# mboard.net
KiCad netlist of a schematic drawn in Altium Designer
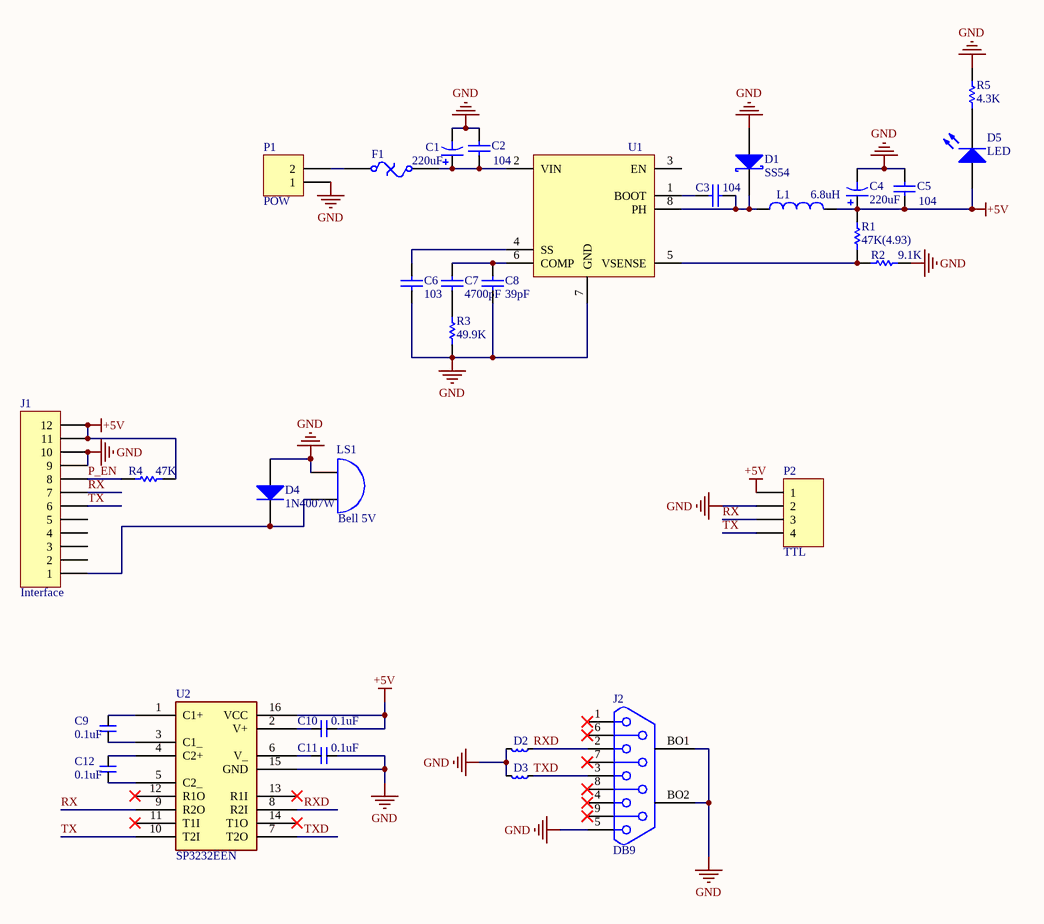
[diagram p0: mboard.SchDoc]

(export (version "E")
  (design (tool "Eeschema 10.0.6"))
  (components
    (comp (ref "C1")
      (value "220uF")
      (footprint "C8x10-SMD")
      (description "Polarized Capacitor (Radial)")
      (fields (field (name "Comment") "Cap Pol1") (field (name "PUBLISHER") "Altium Limited"))
      (libsource (lib "Miscellaneous Devices") (part "Cap Pol1"))
    )
    (comp (ref "C2")
      (value "104")
      (footprint "0603C")
      (description "Capacitor")
      (fields (field (name "Comment") "Cap") (field (name "PUBLISHER") "Altium Limited"))
      (libsource (lib "Miscellaneous Devices") (part "Cap"))
    )
    (comp (ref "C3")
      (value "104")
      (footprint "0603C")
      (description "Capacitor")
      (fields (field (name "Comment") "Cap") (field (name "PUBLISHER") "Altium Limited"))
      (libsource (lib "Miscellaneous Devices") (part "Cap"))
    )
    (comp (ref "C4")
      (value "220uF")
      (footprint "C6.3x5.4-SMD")
      (description "Polarized Capacitor (Radial)")
      (fields (field (name "Comment") "Cap Pol1") (field (name "PUBLISHER") "Altium Limited"))
      (libsource (lib "Miscellaneous Devices") (part "Cap Pol1"))
    )
    (comp (ref "C5")
      (value "104")
      (footprint "0603C")
      (description "Capacitor")
      (fields (field (name "Comment") "Cap") (field (name "PUBLISHER") "Altium Limited"))
      (libsource (lib "Miscellaneous Devices") (part "Cap"))
    )
    (comp (ref "C6")
      (value "103")
      (footprint "0603C")
      (description "Capacitor")
      (fields (field (name "Comment") "Cap") (field (name "PUBLISHER") "Altium Limited"))
      (libsource (lib "Miscellaneous Devices") (part "Cap"))
    )
    (comp (ref "C7")
      (value "4700pF")
      (footprint "0603C")
      (description "Capacitor")
      (fields (field (name "Comment") "Cap") (field (name "PUBLISHER") "Altium Limited"))
      (libsource (lib "Miscellaneous Devices") (part "Cap"))
    )
    (comp (ref "C8")
      (value "39pF")
      (footprint "0603C")
      (description "Capacitor")
      (fields (field (name "Comment") "Cap") (field (name "PUBLISHER") "Altium Limited"))
      (libsource (lib "Miscellaneous Devices") (part "Cap"))
    )
    (comp (ref "C9")
      (value "0.1uF")
      (footprint "0603C")
      (description "电容")
      (libsource (lib "LDT-SCH") (part "电容"))
    )
    (comp (ref "C10")
      (value "0.1uF")
      (footprint "0603C")
      (description "电容")
      (libsource (lib "LDT-SCH") (part "电容"))
    )
    (comp (ref "C11")
      (value "0.1uF")
      (footprint "0603C")
      (description "电容")
      (libsource (lib "LDT-SCH") (part "电容"))
    )
    (comp (ref "C12")
      (value "0.1uF")
      (footprint "0603C")
      (description "电容")
      (libsource (lib "LDT-SCH") (part "电容"))
    )
    (comp (ref "D1")
      (value "SS54")
      (footprint "SMA")
      (description "Schottky Diode")
      (fields (field (name "PUBLISHER") "Altium Limited"))
      (libsource (lib "Miscellaneous Devices") (part "D Schottky"))
    )
    (comp (ref "D2") (value "ESD") (footprint "0603L") (libsource (lib "LDT-SCH") (part "电感")))
    (comp (ref "D3") (value "ESD") (footprint "0603L") (libsource (lib "LDT-SCH") (part "电感")))
    (comp (ref "D4")
      (value "1N4007W")
      (footprint "SOD-123")
      (description "3 Amp Medium Power Silicon Rectifier Diode")
      (fields (field (name "PUBLISHER") "Altium Limited"))
      (libsource (lib "Miscellaneous Devices") (part "Diode 1N5408"))
    )
    (comp (ref "D5")
      (value "LED")
      (footprint "0603-LED")
      (description "Typical RED GaAs LED")
      (fields (field (name "PUBLISHER") "Altium Limited"))
      (libsource (lib "Miscellaneous Devices") (part "LED1"))
    )
    (comp (ref "F1")
      (value "Fuse Thermal")
      (footprint "1812F")
      (description "Thermal Fuse")
      (fields (field (name "PUBLISHER") "Altium Limited"))
      (libsource (lib "Miscellaneous Devices") (part "Fuse Thermal"))
    )
    (comp (ref "J1")
      (value "Interface")
      (footprint "1.25-12P")
      (description "Header, 12-Pin")
      (fields (field (name "PUBLISHER") "Altium Limited"))
      (libsource (lib "Miscellaneous Connectors") (part "Header 12"))
    )
    (comp (ref "J2") (value "DB9") (footprint "DB-9/M") (libsource (lib "LDT-SCH") (part "DB9")))
    (comp (ref "L1")
      (value "6.8uH")
      (footprint "L-6045")
      (description "Inductor")
      (fields (field (name "PUBLISHER") "Altium Limited"))
      (libsource (lib "Miscellaneous Devices") (part "Inductor"))
    )
    (comp (ref "LS1")
      (value "Bell 5V")
      (footprint "BEEP-9x5.5")
      (description "Electrical Bell")
      (fields (field (name "Comment") "Bell") (field (name "PUBLISHER") "Altium Limited"))
      (libsource (lib "Miscellaneous Devices") (part "Bell"))
    )
    (comp (ref "P1")
      (value "POW")
      (footprint "DC-5525")
      (description "Header, 2-Pin")
      (fields (field (name "PUBLISHER") "Altium Limited"))
      (libsource (lib "Miscellaneous Connectors") (part "Header 2"))
    )
    (comp (ref "P2")
      (value "TTL")
      (footprint "XH2.54-4P")
      (description "Header, 4-Pin")
      (fields (field (name "PUBLISHER") "Altium Limited"))
      (libsource (lib "Miscellaneous Connectors") (part "Header 4"))
    )
    (comp (ref "R1")
      (value "47K(4.93)")
      (footprint "0603R")
      (description "Semiconductor Resistor")
      (fields (field (name "Comment") "Res Semi") (field (name "PUBLISHER") "Altium Limited"))
      (libsource (lib "Miscellaneous Devices") (part "Res Semi"))
    )
    (comp (ref "R2")
      (value "9.1K")
      (footprint "0603R")
      (description "Semiconductor Resistor")
      (fields (field (name "Comment") "Res Semi") (field (name "PUBLISHER") "Altium Limited"))
      (libsource (lib "Miscellaneous Devices") (part "Res Semi"))
    )
    (comp (ref "R3")
      (value "49.9K")
      (footprint "0603R")
      (description "Semiconductor Resistor")
      (fields (field (name "Comment") "Res Semi") (field (name "PUBLISHER") "Altium Limited"))
      (libsource (lib "Miscellaneous Devices") (part "Res Semi"))
    )
    (comp (ref "R4")
      (value "47K")
      (footprint "0603R")
      (description "Semiconductor Resistor")
      (fields (field (name "Comment") "Res Semi") (field (name "PUBLISHER") "Altium Limited"))
      (libsource (lib "Miscellaneous Devices") (part "Res Semi"))
    )
    (comp (ref "R5")
      (value "4.3K")
      (footprint "0603R")
      (description "Resistor")
      (fields (field (name "Comment") "Res1") (field (name "PUBLISHER") "Altium Limited"))
      (libsource (lib "Miscellaneous Devices") (part "Res1"))
    )
    (comp (ref "U1") (value "TPS54331") (footprint "SOP8-POW") (libsource (lib "Tank") (part "TPS54331")))
    (comp (ref "U2")
      (value "SP3232EEN")
      (footprint "SOIC16-1.27")
      (libsource (lib "LDT-SCH") (part "MAX232ESE"))
    )
  )
  (nets
    (net (code "1") (name "+5V") (class "Default")
      (node (ref "C10") (pin "2") (pintype "passive"))
      (node (ref "C4") (pin "1") (pinfunction "1_1") (pintype "passive"))
      (node (ref "C5") (pin "1") (pinfunction "1_1") (pintype "passive"))
      (node (ref "D5") (pin "1") (pinfunction "A_1") (pintype "passive"))
      (node (ref "J1") (pin "11") (pinfunction "11_11") (pintype "passive"))
      (node (ref "J1") (pin "12") (pinfunction "12_12") (pintype "passive"))
      (node (ref "L1") (pin "2") (pinfunction "2_2") (pintype "passive"))
      (node (ref "P2") (pin "1") (pinfunction "1_1") (pintype "passive"))
      (node (ref "R1") (pin "2") (pinfunction "2_2") (pintype "passive"))
      (node (ref "R4") (pin "1") (pinfunction "1_1") (pintype "passive"))
      (node (ref "U2") (pin "16") (pinfunction "VCC_16") (pintype "passive"))
    )
    (net (code "2") (name "/P_EN") (class "Default")
      (node (ref "J1") (pin "8") (pinfunction "8_8") (pintype "passive"))
      (node (ref "R4") (pin "2") (pinfunction "2_2") (pintype "passive"))
    )
    (net (code "3") (name "/RX") (class "Default")
      (node (ref "J1") (pin "7") (pinfunction "7_7") (pintype "passive"))
      (node (ref "P2") (pin "3") (pinfunction "3_3") (pintype "passive"))
      (node (ref "U2") (pin "9") (pinfunction "R2O_9") (pintype "passive"))
    )
    (net (code "4") (name "/RXD") (class "Default")
      (node (ref "D2") (pin "1") (pintype "passive"))
      (node (ref "J2") (pin "2") (pinfunction "2_2") (pintype "passive"))
      (node (ref "U2") (pin "8") (pinfunction "R2I_8") (pintype "passive"))
    )
    (net (code "5") (name "/TX") (class "Default")
      (node (ref "J1") (pin "6") (pinfunction "6_6") (pintype "passive"))
      (node (ref "P2") (pin "4") (pinfunction "4_4") (pintype "passive"))
      (node (ref "U2") (pin "10") (pinfunction "T2I_10") (pintype "passive"))
    )
    (net (code "6") (name "/TXD") (class "Default")
      (node (ref "D3") (pin "1") (pintype "passive"))
      (node (ref "J2") (pin "3") (pinfunction "3_3") (pintype "passive"))
      (node (ref "U2") (pin "7") (pinfunction "T2O_7") (pintype "passive"))
    )
    (net (code "7") (name "GND") (class "Default")
      (node (ref "C1") (pin "2") (pinfunction "2_2") (pintype "passive"))
      (node (ref "C11") (pin "2") (pintype "passive"))
      (node (ref "C2") (pin "2") (pinfunction "2_2") (pintype "passive"))
      (node (ref "C4") (pin "2") (pinfunction "2_2") (pintype "passive"))
      (node (ref "C5") (pin "2") (pinfunction "2_2") (pintype "passive"))
      (node (ref "C6") (pin "2") (pinfunction "2_2") (pintype "passive"))
      (node (ref "C8") (pin "1") (pinfunction "1_1") (pintype "passive"))
      (node (ref "D1") (pin "1") (pinfunction "A_1") (pintype "passive"))
      (node (ref "D2") (pin "2") (pintype "passive"))
      (node (ref "D3") (pin "2") (pintype "passive"))
      (node (ref "D4") (pin "1") (pinfunction "A_1") (pintype "passive"))
      (node (ref "J1") (pin "10") (pinfunction "10_10") (pintype "passive"))
      (node (ref "J1") (pin "9") (pinfunction "9_9") (pintype "passive"))
      (node (ref "J2") (pin "5") (pinfunction "5_5") (pintype "passive"))
      (node (ref "J2") (pin "BO1") (pinfunction "BO1_BO1") (pintype "passive"))
      (node (ref "J2") (pin "BO2") (pinfunction "BO2_BO2") (pintype "passive"))
      (node (ref "LS1") (pin "1") (pinfunction "A_1") (pintype "passive"))
      (node (ref "P1") (pin "1") (pinfunction "1_1") (pintype "passive"))
      (node (ref "P2") (pin "2") (pinfunction "2_2") (pintype "passive"))
      (node (ref "R2") (pin "2") (pinfunction "2_2") (pintype "passive"))
      (node (ref "R3") (pin "1") (pinfunction "1_1") (pintype "passive"))
      (node (ref "R5") (pin "1") (pinfunction "1_1") (pintype "passive"))
      (node (ref "U1") (pin "7") (pinfunction "GND_7") (pintype "passive"))
      (node (ref "U2") (pin "15") (pinfunction "GND_15") (pintype "passive"))
    )
    (net (code "8") (name "Net-(C7-Pad1)") (class "Default")
      (node (ref "C7") (pin "1") (pinfunction "1_1") (pintype "passive"))
      (node (ref "R3") (pin "2") (pinfunction "2_2") (pintype "passive"))
    )
    (net (code "9") (name "Net-(D1-K)") (class "Default")
      (node (ref "C3") (pin "1") (pinfunction "1_1") (pintype "passive"))
      (node (ref "D1") (pin "2") (pinfunction "K_2") (pintype "passive"))
      (node (ref "L1") (pin "1") (pinfunction "1_1") (pintype "passive"))
      (node (ref "U1") (pin "8") (pinfunction "PH_8") (pintype "passive"))
    )
    (net (code "10") (name "Net-(D4-K)") (class "Default")
      (node (ref "D4") (pin "2") (pinfunction "K_2") (pintype "passive"))
      (node (ref "J1") (pin "1") (pinfunction "1_1") (pintype "passive"))
      (node (ref "LS1") (pin "2") (pinfunction "B_2") (pintype "passive"))
    )
    (net (code "11") (name "Net-(D5-K)") (class "Default")
      (node (ref "D5") (pin "2") (pinfunction "K_2") (pintype "passive"))
      (node (ref "R5") (pin "2") (pinfunction "2_2") (pintype "passive"))
    )
    (net (code "12") (name "Net-(F1-Pad1)") (class "Default")
      (node (ref "F1") (pin "1") (pinfunction "1_1") (pintype "passive"))
      (node (ref "P1") (pin "2") (pinfunction "2_2") (pintype "passive"))
    )
    (net (code "13") (name "Net-(U1-BOOT)") (class "Default")
      (node (ref "C3") (pin "2") (pinfunction "2_2") (pintype "passive"))
      (node (ref "U1") (pin "1") (pinfunction "BOOT_1") (pintype "passive"))
    )
    (net (code "14") (name "Net-(U1-COMP)") (class "Default")
      (node (ref "C7") (pin "2") (pinfunction "2_2") (pintype "passive"))
      (node (ref "C8") (pin "2") (pinfunction "2_2") (pintype "passive"))
      (node (ref "U1") (pin "6") (pinfunction "COMP_6") (pintype "passive"))
    )
    (net (code "15") (name "Net-(U1-SS)") (class "Default")
      (node (ref "C6") (pin "1") (pinfunction "1_1") (pintype "passive"))
      (node (ref "U1") (pin "4") (pinfunction "SS_4") (pintype "passive"))
    )
    (net (code "16") (name "Net-(U1-VIN)") (class "Default")
      (node (ref "C1") (pin "1") (pinfunction "1_1") (pintype "passive"))
      (node (ref "C2") (pin "1") (pinfunction "1_1") (pintype "passive"))
      (node (ref "F1") (pin "2") (pinfunction "2_2") (pintype "passive"))
      (node (ref "U1") (pin "2") (pinfunction "VIN_2") (pintype "passive"))
    )
    (net (code "17") (name "Net-(U1-VSENSE)") (class "Default")
      (node (ref "R1") (pin "1") (pinfunction "1_1") (pintype "passive"))
      (node (ref "R2") (pin "1") (pinfunction "1_1") (pintype "passive"))
      (node (ref "U1") (pin "5") (pinfunction "VSENSE_5") (pintype "passive"))
    )
    (net (code "18") (name "Net-(U2-C1+)") (class "Default")
      (node (ref "C9") (pin "1") (pintype "passive"))
      (node (ref "U2") (pin "1") (pinfunction "C1+_1") (pintype "passive"))
    )
    (net (code "19") (name "Net-(U2-C1_)") (class "Default")
      (node (ref "C9") (pin "2") (pintype "passive"))
      (node (ref "U2") (pin "3") (pinfunction "C1__3") (pintype "passive"))
    )
    (net (code "20") (name "Net-(U2-C2+)") (class "Default")
      (node (ref "C12") (pin "1") (pintype "passive"))
      (node (ref "U2") (pin "4") (pinfunction "C2+_4") (pintype "passive"))
    )
    (net (code "21") (name "Net-(U2-C2_)") (class "Default")
      (node (ref "C12") (pin "2") (pintype "passive"))
      (node (ref "U2") (pin "5") (pinfunction "C2__5") (pintype "passive"))
    )
    (net (code "22") (name "Net-(U2-V+)") (class "Default")
      (node (ref "C10") (pin "1") (pintype "passive"))
      (node (ref "U2") (pin "2") (pinfunction "V+_2") (pintype "passive"))
    )
    (net (code "23") (name "Net-(U2-V_)") (class "Default")
      (node (ref "C11") (pin "1") (pintype "passive"))
      (node (ref "U2") (pin "6") (pinfunction "V__6") (pintype "passive"))
    )
    (net (code "24") (name "unconnected-(J1-Pad2)") (class "Default")
      (node (ref "J1") (pin "2") (pinfunction "2_2") (pintype "passive"))
    )
    (net (code "25") (name "unconnected-(J1-Pad3)") (class "Default")
      (node (ref "J1") (pin "3") (pinfunction "3_3") (pintype "passive"))
    )
    (net (code "26") (name "unconnected-(J1-Pad4)") (class "Default")
      (node (ref "J1") (pin "4") (pinfunction "4_4") (pintype "passive"))
    )
    (net (code "27") (name "unconnected-(J1-Pad5)") (class "Default")
      (node (ref "J1") (pin "5") (pinfunction "5_5") (pintype "passive"))
    )
    (net (code "28") (name "unconnected-(J2-Pad1)") (class "Default")
      (node (ref "J2") (pin "1") (pinfunction "1_1") (pintype "passive+no_connect"))
    )
    (net (code "29") (name "unconnected-(J2-Pad4)") (class "Default")
      (node (ref "J2") (pin "4") (pinfunction "4_4") (pintype "passive+no_connect"))
    )
    (net (code "30") (name "unconnected-(J2-Pad6)") (class "Default")
      (node (ref "J2") (pin "6") (pinfunction "6_6") (pintype "passive+no_connect"))
    )
    (net (code "31") (name "unconnected-(J2-Pad7)") (class "Default")
      (node (ref "J2") (pin "7") (pinfunction "7_7") (pintype "passive+no_connect"))
    )
    (net (code "32") (name "unconnected-(J2-Pad8)") (class "Default")
      (node (ref "J2") (pin "8") (pinfunction "8_8") (pintype "passive+no_connect"))
    )
    (net (code "33") (name "unconnected-(J2-Pad9)") (class "Default")
      (node (ref "J2") (pin "9") (pinfunction "9_9") (pintype "passive+no_connect"))
    )
    (net (code "34") (name "unconnected-(U1-EN-Pad3)") (class "Default")
      (node (ref "U1") (pin "3") (pinfunction "EN_3") (pintype "passive"))
    )
    (net (code "35") (name "unconnected-(U2-R1I-Pad13)") (class "Default")
      (node (ref "U2") (pin "13") (pinfunction "R1I_13") (pintype "passive+no_connect"))
    )
    (net (code "36") (name "unconnected-(U2-R1O-Pad12)") (class "Default")
      (node (ref "U2") (pin "12") (pinfunction "R1O_12") (pintype "passive+no_connect"))
    )
    (net (code "37") (name "unconnected-(U2-T1I-Pad11)") (class "Default")
      (node (ref "U2") (pin "11") (pinfunction "T1I_11") (pintype "passive+no_connect"))
    )
    (net (code "38") (name "unconnected-(U2-T1O-Pad14)") (class "Default")
      (node (ref "U2") (pin "14") (pinfunction "T1O_14") (pintype "passive+no_connect"))
    )
  )
)
